# Sheet1.net
KiCad netlist of a schematic drawn in Altium Designer
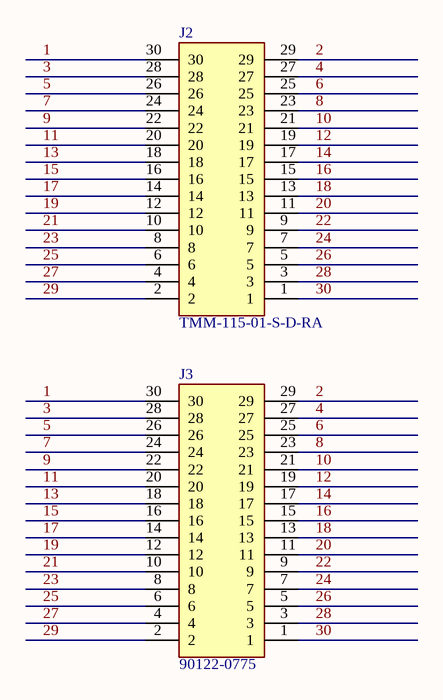
[diagram p0: Sheet1.SchDoc]

(export (version "E")
  (design (tool "Eeschema 10.0.6"))
  (components
    (comp (ref "J2")
      (value "TMM-115-01-S-D-RA")
      (footprint "SamacSys:TMM11501SDRA")
      (description "Connector")
      (fields (field (name "MOUSER PART NUMBER") "200-TMM11501SDRA"))
      (libsource (lib "*") (part "TMM-115-01-S-D-RA"))
    )
    (comp (ref "J3")
      (value "90122-0775")
      (footprint "SamacSys:HDRRA30W65P254_2X15_3802X250X635P")
      (description "Connector")
      (fields (field (name "MOUSER PART NUMBER") "538-90122-0775"))
      (libsource (lib "*") (part "90122-0775"))
    )
  )
  (nets
    (net (code "1") (name "/1") (class "Default")
      (node (ref "J2") (pin "30") (pinfunction "30_30") (pintype "passive"))
      (node (ref "J3") (pin "30") (pinfunction "30_30") (pintype "passive"))
    )
    (net (code "2") (name "/2") (class "Default")
      (node (ref "J2") (pin "29") (pinfunction "29_29") (pintype "passive"))
      (node (ref "J3") (pin "29") (pinfunction "29_29") (pintype "passive"))
    )
    (net (code "3") (name "/3") (class "Default")
      (node (ref "J2") (pin "28") (pinfunction "28_28") (pintype "passive"))
      (node (ref "J3") (pin "28") (pinfunction "28_28") (pintype "passive"))
    )
    (net (code "4") (name "/4") (class "Default")
      (node (ref "J2") (pin "27") (pinfunction "27_27") (pintype "passive"))
      (node (ref "J3") (pin "27") (pinfunction "27_27") (pintype "passive"))
    )
    (net (code "5") (name "/5") (class "Default")
      (node (ref "J2") (pin "26") (pinfunction "26_26") (pintype "passive"))
      (node (ref "J3") (pin "26") (pinfunction "26_26") (pintype "passive"))
    )
    (net (code "6") (name "/6") (class "Default")
      (node (ref "J2") (pin "25") (pinfunction "25_25") (pintype "passive"))
      (node (ref "J3") (pin "25") (pinfunction "25_25") (pintype "passive"))
    )
    (net (code "7") (name "/7") (class "Default")
      (node (ref "J2") (pin "24") (pinfunction "24_24") (pintype "passive"))
      (node (ref "J3") (pin "24") (pinfunction "24_24") (pintype "passive"))
    )
    (net (code "8") (name "/8") (class "Default")
      (node (ref "J2") (pin "23") (pinfunction "23_23") (pintype "passive"))
      (node (ref "J3") (pin "23") (pinfunction "23_23") (pintype "passive"))
    )
    (net (code "9") (name "/9") (class "Default")
      (node (ref "J2") (pin "22") (pinfunction "22_22") (pintype "passive"))
      (node (ref "J3") (pin "22") (pinfunction "22_22") (pintype "passive"))
    )
    (net (code "10") (name "/10") (class "Default")
      (node (ref "J2") (pin "21") (pinfunction "21_21") (pintype "passive"))
      (node (ref "J3") (pin "21") (pinfunction "21_21") (pintype "passive"))
    )
    (net (code "11") (name "/11") (class "Default")
      (node (ref "J2") (pin "20") (pinfunction "20_20") (pintype "passive"))
      (node (ref "J3") (pin "20") (pinfunction "20_20") (pintype "passive"))
    )
    (net (code "12") (name "/12") (class "Default")
      (node (ref "J2") (pin "19") (pinfunction "19_19") (pintype "passive"))
      (node (ref "J3") (pin "19") (pinfunction "19_19") (pintype "passive"))
    )
    (net (code "13") (name "/13") (class "Default")
      (node (ref "J2") (pin "18") (pinfunction "18_18") (pintype "passive"))
      (node (ref "J3") (pin "18") (pinfunction "18_18") (pintype "passive"))
    )
    (net (code "14") (name "/14") (class "Default")
      (node (ref "J2") (pin "17") (pinfunction "17_17") (pintype "passive"))
      (node (ref "J3") (pin "17") (pinfunction "17_17") (pintype "passive"))
    )
    (net (code "15") (name "/15") (class "Default")
      (node (ref "J2") (pin "16") (pinfunction "16_16") (pintype "passive"))
      (node (ref "J3") (pin "16") (pinfunction "16_16") (pintype "passive"))
    )
    (net (code "16") (name "/16") (class "Default")
      (node (ref "J2") (pin "15") (pinfunction "15_15") (pintype "passive"))
      (node (ref "J3") (pin "15") (pinfunction "15_15") (pintype "passive"))
    )
    (net (code "17") (name "/17") (class "Default")
      (node (ref "J2") (pin "14") (pinfunction "14_14") (pintype "passive"))
      (node (ref "J3") (pin "14") (pinfunction "14_14") (pintype "passive"))
    )
    (net (code "18") (name "/18") (class "Default")
      (node (ref "J2") (pin "13") (pinfunction "13_13") (pintype "passive"))
      (node (ref "J3") (pin "13") (pinfunction "13_13") (pintype "passive"))
    )
    (net (code "19") (name "/19") (class "Default")
      (node (ref "J2") (pin "12") (pinfunction "12_12") (pintype "passive"))
      (node (ref "J3") (pin "12") (pinfunction "12_12") (pintype "passive"))
    )
    (net (code "20") (name "/20") (class "Default")
      (node (ref "J2") (pin "11") (pinfunction "11_11") (pintype "passive"))
      (node (ref "J3") (pin "11") (pinfunction "11_11") (pintype "passive"))
    )
    (net (code "21") (name "/21") (class "Default")
      (node (ref "J2") (pin "10") (pinfunction "10_10") (pintype "passive"))
      (node (ref "J3") (pin "10") (pinfunction "10_10") (pintype "passive"))
    )
    (net (code "22") (name "/22") (class "Default")
      (node (ref "J2") (pin "9") (pinfunction "9_9") (pintype "passive"))
      (node (ref "J3") (pin "9") (pinfunction "9_9") (pintype "passive"))
    )
    (net (code "23") (name "/23") (class "Default")
      (node (ref "J2") (pin "8") (pinfunction "8_8") (pintype "passive"))
      (node (ref "J3") (pin "8") (pinfunction "8_8") (pintype "passive"))
    )
    (net (code "24") (name "/24") (class "Default")
      (node (ref "J2") (pin "7") (pinfunction "7_7") (pintype "passive"))
      (node (ref "J3") (pin "7") (pinfunction "7_7") (pintype "passive"))
    )
    (net (code "25") (name "/25") (class "Default")
      (node (ref "J2") (pin "6") (pinfunction "6_6") (pintype "passive"))
      (node (ref "J3") (pin "6") (pinfunction "6_6") (pintype "passive"))
    )
    (net (code "26") (name "/26") (class "Default")
      (node (ref "J2") (pin "5") (pinfunction "5_5") (pintype "passive"))
      (node (ref "J3") (pin "5") (pinfunction "5_5") (pintype "passive"))
    )
    (net (code "27") (name "/27") (class "Default")
      (node (ref "J2") (pin "4") (pinfunction "4_4") (pintype "passive"))
      (node (ref "J3") (pin "4") (pinfunction "4_4") (pintype "passive"))
    )
    (net (code "28") (name "/28") (class "Default")
      (node (ref "J2") (pin "3") (pinfunction "3_3") (pintype "passive"))
      (node (ref "J3") (pin "3") (pinfunction "3_3") (pintype "passive"))
    )
    (net (code "29") (name "/29") (class "Default")
      (node (ref "J2") (pin "2") (pinfunction "2_2") (pintype "passive"))
      (node (ref "J3") (pin "2") (pinfunction "2_2") (pintype "passive"))
    )
    (net (code "30") (name "/30") (class "Default")
      (node (ref "J2") (pin "1") (pinfunction "1_1") (pintype "passive"))
      (node (ref "J3") (pin "1") (pinfunction "1_1") (pintype "passive"))
    )
  )
)
